# DRL.net
KiCad netlist of a schematic drawn in Altium Designer
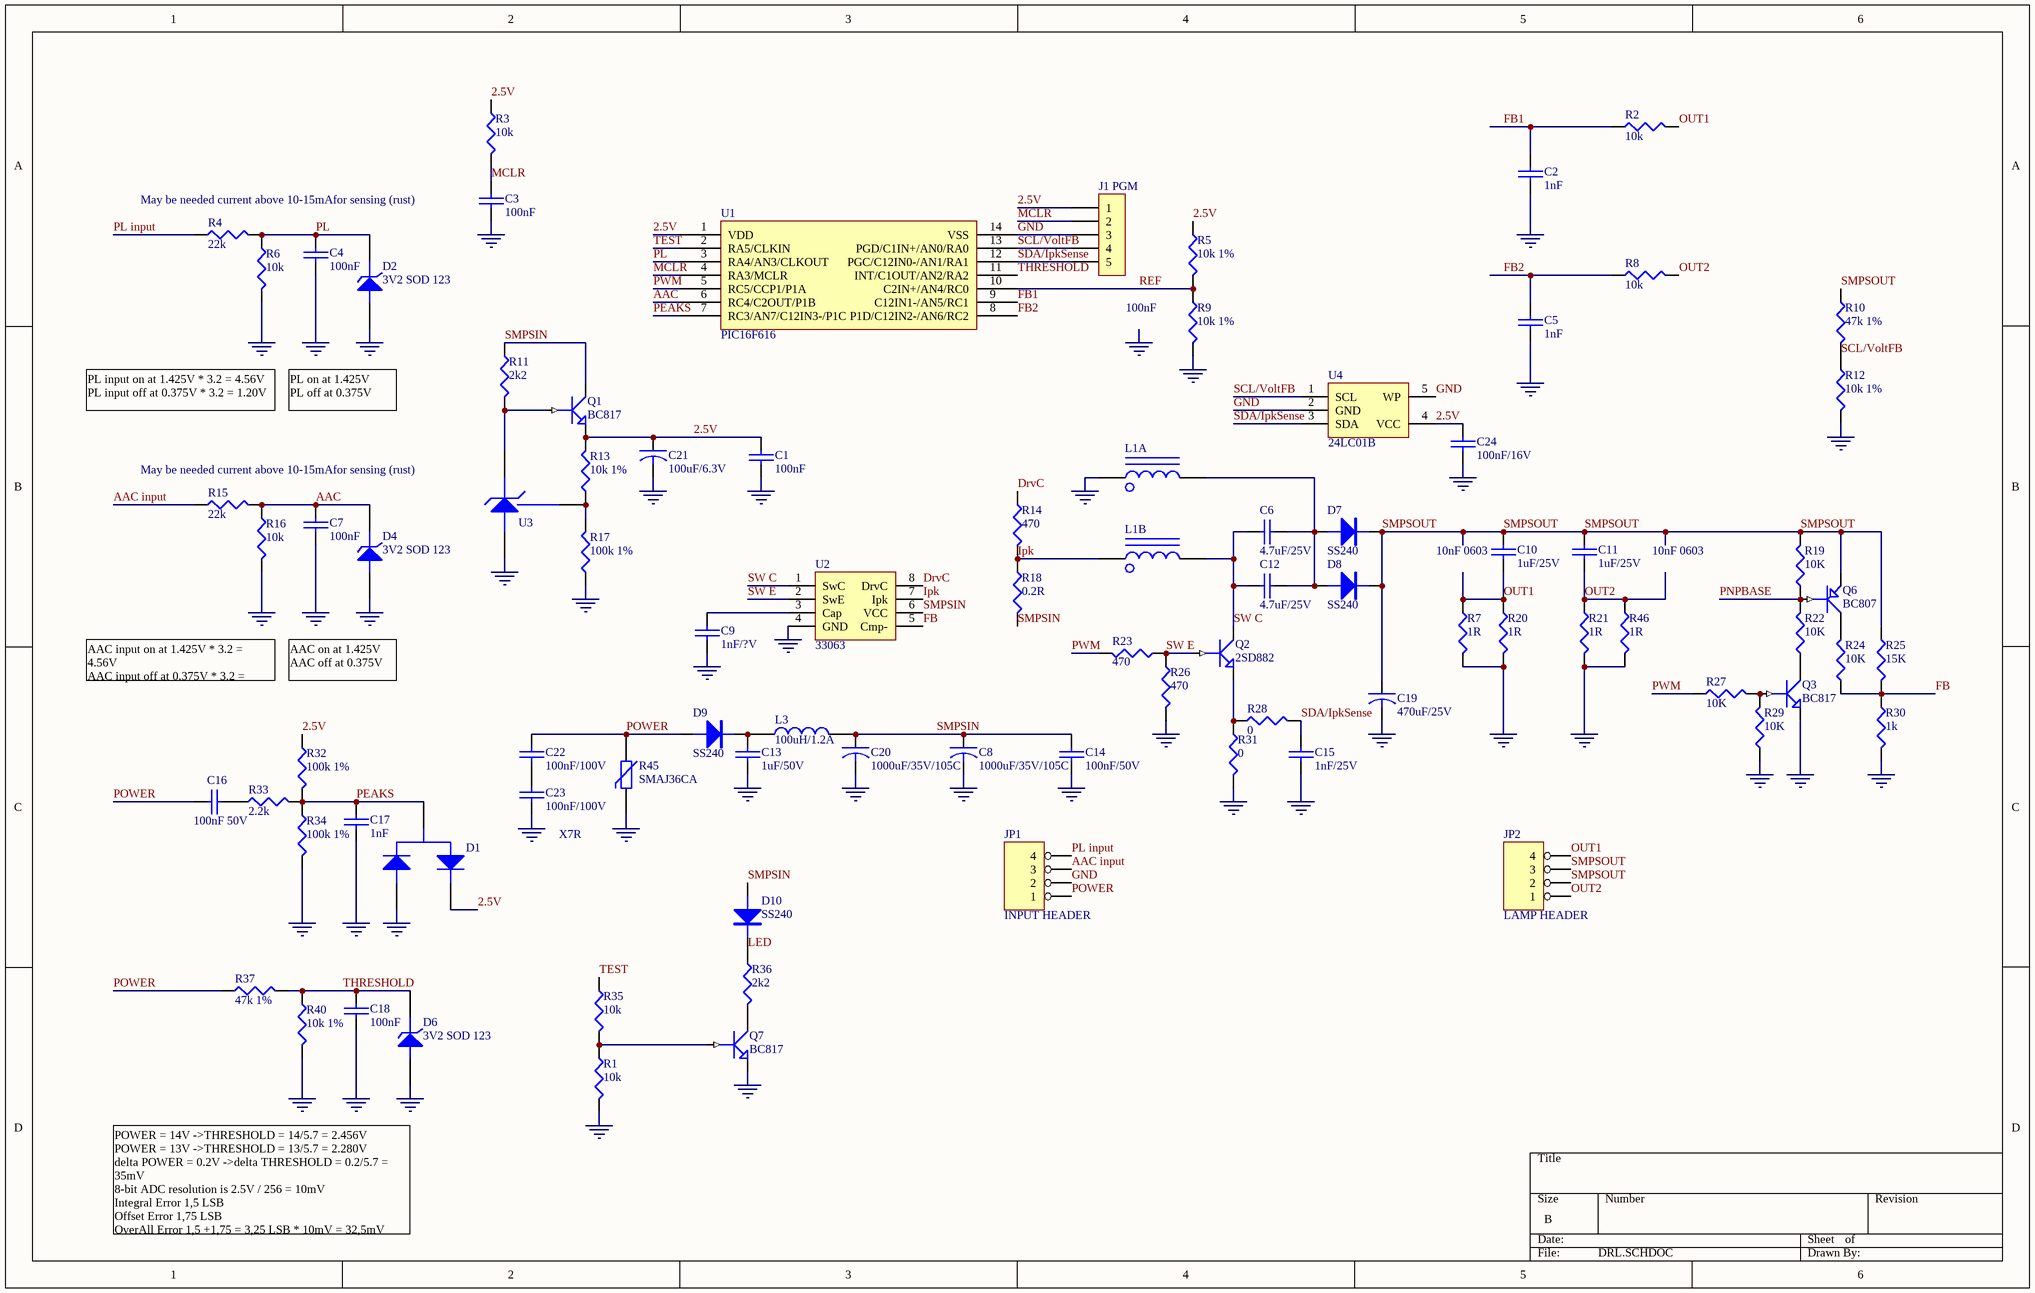
[diagram p0: DRL.SCHDOC]

(export (version "E")
  (design (tool "Eeschema 10.0.6"))
  (components
    (comp (ref "C1")
      (value "100nF")
      (footprint "0603")
      (description "Capacitor")
      (libsource (lib "Miscellaneous Devices") (part "CAP"))
    )
    (comp (ref "C2")
      (value "1nF")
      (footprint "0603")
      (description "Capacitor")
      (libsource (lib "Miscellaneous Devices") (part "CAP"))
    )
    (comp (ref "C3")
      (value "100nF")
      (footprint "0603")
      (description "Capacitor")
      (libsource (lib "Miscellaneous Devices") (part "CAP"))
    )
    (comp (ref "C4")
      (value "100nF")
      (footprint "0603")
      (description "Capacitor")
      (libsource (lib "Miscellaneous Devices") (part "CAP"))
    )
    (comp (ref "C5")
      (value "1nF")
      (footprint "0603")
      (description "Capacitor")
      (libsource (lib "Miscellaneous Devices") (part "CAP"))
    )
    (comp (ref "C6")
      (value "4.7uF/25V")
      (footprint "0805")
      (description "Capacitor")
      (libsource (lib "Miscellaneous Devices") (part "CAP"))
    )
    (comp (ref "C7")
      (value "100nF")
      (footprint "0603")
      (description "Capacitor")
      (libsource (lib "Miscellaneous Devices") (part "CAP"))
    )
    (comp (ref "C8")
      (value "1000uF/35V/105C")
      (footprint "RA 13mm")
      (description "Capacitor")
      (libsource (lib "Miscellaneous Devices") (part "CAPACITOR"))
    )
    (comp (ref "C9")
      (value "1nF/?V")
      (footprint "0603")
      (description "Capacitor")
      (libsource (lib "Miscellaneous Devices") (part "CAP"))
    )
    (comp (ref "C10")
      (value "1uF/25V")
      (footprint "0805")
      (description "Capacitor")
      (libsource (lib "Miscellaneous Devices") (part "CAP"))
    )
    (comp (ref "C11")
      (value "1uF/25V")
      (footprint "0805")
      (description "Capacitor")
      (libsource (lib "Miscellaneous Devices") (part "CAP"))
    )
    (comp (ref "C12")
      (value "4.7uF/25V")
      (footprint "0805")
      (description "Capacitor")
      (libsource (lib "Miscellaneous Devices") (part "CAP"))
    )
    (comp (ref "C13")
      (value "1uF/50V")
      (footprint "0805")
      (description "Capacitor")
      (libsource (lib "Miscellaneous Devices") (part "CAP"))
    )
    (comp (ref "C14")
      (value "100nF/50V")
      (footprint "0603")
      (description "Capacitor")
      (libsource (lib "Miscellaneous Devices") (part "CAP"))
    )
    (comp (ref "C15")
      (value "1nF/25V")
      (footprint "0603")
      (description "Capacitor")
      (libsource (lib "Miscellaneous Devices") (part "CAP"))
    )
    (comp (ref "C16")
      (value "100nF 50V")
      (footprint "0805")
      (description "Capacitor")
      (libsource (lib "Miscellaneous Devices") (part "CAP"))
    )
    (comp (ref "C17")
      (value "1nF")
      (footprint "0603")
      (description "Capacitor")
      (libsource (lib "Miscellaneous Devices") (part "CAP"))
    )
    (comp (ref "C18")
      (value "100nF")
      (footprint "0603")
      (description "Capacitor")
      (libsource (lib "Miscellaneous Devices") (part "CAP"))
    )
    (comp (ref "C19")
      (value "470uF/25V")
      (footprint "CS 10.3")
      (description "Capacitor")
      (libsource (lib "Miscellaneous Devices") (part "CAPACITOR"))
    )
    (comp (ref "C20")
      (value "1000uF/35V/105C")
      (footprint "RA 13mm")
      (description "Capacitor")
      (libsource (lib "Miscellaneous Devices") (part "CAPACITOR"))
    )
    (comp (ref "C21")
      (value "100uF/6.3V")
      (footprint "CS 6.6")
      (description "Capacitor")
      (libsource (lib "Miscellaneous Devices") (part "CAPACITOR"))
    )
    (comp (ref "C22")
      (value "100nF/100V")
      (footprint "0603")
      (description "Capacitor")
      (libsource (lib "Miscellaneous Devices") (part "CAP"))
    )
    (comp (ref "C23")
      (value "100nF/100V")
      (footprint "0603")
      (description "Capacitor")
      (libsource (lib "Miscellaneous Devices") (part "CAP"))
    )
    (comp (ref "C24")
      (value "100nF/16V")
      (footprint "0603")
      (description "Capacitor")
      (libsource (lib "Miscellaneous Devices") (part "CAP"))
    )
    (comp (ref "D1")
      (value "DUAL DIODE BAV99")
      (footprint "SOT-23")
      (libsource (lib "Devices") (part "DUAL DIODE BAV99"))
    )
    (comp (ref "D2")
      (value "3V2 SOD 123")
      (footprint "SOD 123")
      (description "Zener Diode")
      (libsource (lib "Miscellaneous Devices") (part "ZENER3"))
    )
    (comp (ref "D4")
      (value "3V2 SOD 123")
      (footprint "SOD 123")
      (description "Zener Diode")
      (libsource (lib "Miscellaneous Devices") (part "ZENER3"))
    )
    (comp (ref "D6")
      (value "3V2 SOD 123")
      (footprint "SOD 123")
      (description "Zener Diode")
      (libsource (lib "Miscellaneous Devices") (part "ZENER3"))
    )
    (comp (ref "D7")
      (value "SS240")
      (footprint "SMA")
      (description "Diode")
      (libsource (lib "") (part "DIODE_1"))
    )
    (comp (ref "D8")
      (value "SS240")
      (footprint "SMA")
      (description "Diode")
      (libsource (lib "") (part "DIODE_1"))
    )
    (comp (ref "D9")
      (value "SS240")
      (footprint "SMA")
      (description "Diode")
      (libsource (lib "") (part "DIODE_1"))
    )
    (comp (ref "D10")
      (value "SS240")
      (footprint "SIP2")
      (description "Diode")
      (libsource (lib "Miscellaneous Devices") (part "DIODE"))
    )
    (comp (ref "J1")
      (value "PGM")
      (footprint "SIP5 1.27")
      (description "Connector")
      (libsource (lib "Miscellaneous Devices") (part "CON5"))
    )
    (comp (ref "JP1")
      (value "INPUT HEADER")
      (footprint "SIP4 5.1")
      (description "4 Pin Header")
      (libsource (lib "Miscellaneous Devices") (part "4 HEADER"))
    )
    (comp (ref "JP2")
      (value "LAMP HEADER")
      (footprint "SIP4 4.0")
      (description "4 Pin Header")
      (libsource (lib "Miscellaneous Devices") (part "4 HEADER"))
    )
    (comp (ref "L1")
      (value "~")
      (footprint "DUAL IND")
      (libsource (lib "Miscellaneous Devices") (part "INDICTOR SEPIC"))
    )
    (comp (ref "L3")
      (value "100uH/1.2A")
      (footprint "IND SINGLE")
      (libsource (lib "Miscellaneous Devices") (part "INDUCTOR"))
    )
    (comp (ref "Q1")
      (value "BC817")
      (footprint "SOT-23")
      (description "NPN Transistor")
      (libsource (lib "Miscellaneous Devices") (part "NPN1"))
    )
    (comp (ref "Q2")
      (value "2SD882")
      (footprint "SOT-89")
      (description "NPN Transistor")
      (libsource (lib "Miscellaneous Devices") (part "NPN1"))
    )
    (comp (ref "Q3")
      (value "BC817")
      (footprint "SOT-23")
      (description "NPN Transistor")
      (libsource (lib "Miscellaneous Devices") (part "NPN1"))
    )
    (comp (ref "Q6")
      (value "BC807")
      (footprint "SOT-23")
      (description "PNP Transistor")
      (libsource (lib "Miscellaneous Devices") (part "PNP1"))
    )
    (comp (ref "Q7")
      (value "BC817")
      (footprint "SOT-23")
      (description "NPN Transistor")
      (libsource (lib "Miscellaneous Devices") (part "NPN1"))
    )
    (comp (ref "R1") (value "10k") (footprint "0603") (libsource (lib "Miscellaneous Devices") (part "RES1")))
    (comp (ref "R2") (value "10k") (footprint "0603") (libsource (lib "Miscellaneous Devices") (part "RES1")))
    (comp (ref "R3") (value "10k") (footprint "0603") (libsource (lib "Miscellaneous Devices") (part "RES1")))
    (comp (ref "R4") (value "22k") (footprint "0805") (libsource (lib "Miscellaneous Devices") (part "RES1")))
    (comp (ref "R5")
      (value "10k 1%")
      (footprint "0603")
      (libsource (lib "Miscellaneous Devices") (part "RES1"))
    )
    (comp (ref "R6") (value "10k") (footprint "0603") (libsource (lib "Miscellaneous Devices") (part "RES1")))
    (comp (ref "R7") (value "1R") (footprint "1206") (libsource (lib "Miscellaneous Devices") (part "RES1")))
    (comp (ref "R8") (value "10k") (footprint "0603") (libsource (lib "Miscellaneous Devices") (part "RES1")))
    (comp (ref "R9")
      (value "10k 1%")
      (footprint "0603")
      (libsource (lib "Miscellaneous Devices") (part "RES1"))
    )
    (comp (ref "R10")
      (value "47k 1%")
      (footprint "0603")
      (libsource (lib "Miscellaneous Devices") (part "RES1"))
    )
    (comp (ref "R11")
      (value "2k2")
      (footprint "0603")
      (libsource (lib "Miscellaneous Devices") (part "RES1"))
    )
    (comp (ref "R12")
      (value "10k 1%")
      (footprint "0603")
      (libsource (lib "Miscellaneous Devices") (part "RES1"))
    )
    (comp (ref "R13")
      (value "10k 1%")
      (footprint "0603")
      (libsource (lib "Miscellaneous Devices") (part "RES1"))
    )
    (comp (ref "R14")
      (value "470")
      (footprint "0603")
      (libsource (lib "Miscellaneous Devices") (part "RES1"))
    )
    (comp (ref "R15")
      (value "22k")
      (footprint "0805")
      (libsource (lib "Miscellaneous Devices") (part "RES1"))
    )
    (comp (ref "R16")
      (value "10k")
      (footprint "0603")
      (libsource (lib "Miscellaneous Devices") (part "RES1"))
    )
    (comp (ref "R17")
      (value "100k 1%")
      (footprint "0603")
      (libsource (lib "Miscellaneous Devices") (part "RES1"))
    )
    (comp (ref "R18")
      (value "0.2R")
      (footprint "1206")
      (libsource (lib "Miscellaneous Devices") (part "RES1"))
    )
    (comp (ref "R19")
      (value "10K")
      (footprint "0603")
      (libsource (lib "Miscellaneous Devices") (part "RES1"))
    )
    (comp (ref "R20") (value "1R") (footprint "1206") (libsource (lib "Miscellaneous Devices") (part "RES1")))
    (comp (ref "R21") (value "1R") (footprint "1206") (libsource (lib "Miscellaneous Devices") (part "RES1")))
    (comp (ref "R22")
      (value "10K")
      (footprint "0603")
      (libsource (lib "Miscellaneous Devices") (part "RES1"))
    )
    (comp (ref "R23")
      (value "470")
      (footprint "0603")
      (libsource (lib "Miscellaneous Devices") (part "RES1"))
    )
    (comp (ref "R24")
      (value "10K")
      (footprint "0603")
      (libsource (lib "Miscellaneous Devices") (part "RES1"))
    )
    (comp (ref "R25")
      (value "15K")
      (footprint "0603")
      (libsource (lib "Miscellaneous Devices") (part "RES1"))
    )
    (comp (ref "R26")
      (value "470")
      (footprint "0603")
      (libsource (lib "Miscellaneous Devices") (part "RES1"))
    )
    (comp (ref "R27")
      (value "10K")
      (footprint "0603")
      (libsource (lib "Miscellaneous Devices") (part "RES1"))
    )
    (comp (ref "R28") (value "0") (footprint "0603") (libsource (lib "Miscellaneous Devices") (part "RES1")))
    (comp (ref "R29")
      (value "10K")
      (footprint "0603")
      (libsource (lib "Miscellaneous Devices") (part "RES1"))
    )
    (comp (ref "R30") (value "1k") (footprint "0603") (libsource (lib "Miscellaneous Devices") (part "RES1")))
    (comp (ref "R31") (value "0") (footprint "1206") (libsource (lib "Miscellaneous Devices") (part "RES1")))
    (comp (ref "R32")
      (value "100k 1%")
      (footprint "0603")
      (libsource (lib "Miscellaneous Devices") (part "RES1"))
    )
    (comp (ref "R33")
      (value "2.2k")
      (footprint "0603")
      (libsource (lib "Miscellaneous Devices") (part "RES1"))
    )
    (comp (ref "R34")
      (value "100k 1%")
      (footprint "0603")
      (libsource (lib "Miscellaneous Devices") (part "RES1"))
    )
    (comp (ref "R35")
      (value "10k")
      (footprint "0603")
      (libsource (lib "Miscellaneous Devices") (part "RES1"))
    )
    (comp (ref "R36")
      (value "2k2")
      (footprint "0805")
      (libsource (lib "Miscellaneous Devices") (part "RES1"))
    )
    (comp (ref "R37")
      (value "47k 1%")
      (footprint "0603")
      (libsource (lib "Miscellaneous Devices") (part "RES1"))
    )
    (comp (ref "R40")
      (value "10k 1%")
      (footprint "0603")
      (libsource (lib "Miscellaneous Devices") (part "RES1"))
    )
    (comp (ref "R45")
      (value "SMAJ36CA")
      (footprint "SMA")
      (libsource (lib "Miscellaneous Devices") (part "VARISTOR"))
    )
    (comp (ref "R46") (value "1R") (footprint "1206") (libsource (lib "Miscellaneous Devices") (part "RES1")))
    (comp (ref "U1")
      (value "PIC16F616")
      (footprint "SO-14")
      (description "Microchip Microcontroller")
      (libsource (lib "MCU") (part "PIC16F616"))
    )
    (comp (ref "U2")
      (value "33063")
      (footprint "SO-8")
      (description "DC/DC converter")
      (libsource (lib "Devices") (part "34063"))
    )
    (comp (ref "U3") (value "TL431") (footprint "SOT-23") (libsource (lib "Devices") (part "TL431")))
    (comp (ref "U4")
      (value "24LC01B")
      (footprint "SOT23 - 5")
      (libsource (lib "Devices") (part "MEMORY I2C SOT23"))
    )
  )
  (nets
    (net (code "1") (name "/2.5V") (class "Default")
      (node (ref "C1") (pin "1") (pinfunction "1_1") (pintype "passive"))
      (node (ref "C21") (pin "1") (pinfunction "1_1") (pintype "passive"))
      (node (ref "C24") (pin "1") (pinfunction "1_1") (pintype "passive"))
      (node (ref "D1") (pin "3") (pinfunction "K_3") (pintype "passive"))
      (node (ref "J1") (pin "1") (pinfunction "1_1") (pintype "passive"))
      (node (ref "Q1") (pin "3") (pinfunction "E_3") (pintype "passive"))
      (node (ref "R13") (pin "2") (pinfunction "2_2") (pintype "passive"))
      (node (ref "R3") (pin "1") (pinfunction "1_1") (pintype "passive"))
      (node (ref "R32") (pin "1") (pinfunction "1_1") (pintype "passive"))
      (node (ref "R5") (pin "1") (pinfunction "1_1") (pintype "passive"))
      (node (ref "U1") (pin "1") (pinfunction "VDD_1") (pintype "passive"))
      (node (ref "U4") (pin "4") (pinfunction "VCC_4") (pintype "passive"))
    )
    (net (code "2") (name "/AAC") (class "Default")
      (node (ref "C7") (pin "1") (pinfunction "1_1") (pintype "passive"))
      (node (ref "D4") (pin "2") (pinfunction "K_2") (pintype "passive"))
      (node (ref "R15") (pin "2") (pinfunction "2_2") (pintype "passive"))
      (node (ref "R16") (pin "1") (pinfunction "1_1") (pintype "passive"))
      (node (ref "U1") (pin "6") (pinfunction "RC4/C2OUT/P1B_6") (pintype "passive"))
    )
    (net (code "3") (name "/AAC input") (class "Default")
      (node (ref "JP1") (pin "3") (pinfunction "3_3") (pintype "passive"))
      (node (ref "R15") (pin "1") (pinfunction "1_1") (pintype "passive"))
    )
    (net (code "4") (name "/DrvC") (class "Default")
      (node (ref "R14") (pin "1") (pinfunction "1_1") (pintype "passive"))
      (node (ref "U2") (pin "8") (pinfunction "DrvC_8") (pintype "passive"))
    )
    (net (code "5") (name "/FB") (class "Default")
      (node (ref "R24") (pin "1") (pinfunction "1_1") (pintype "passive"))
      (node (ref "R25") (pin "2") (pinfunction "2_2") (pintype "passive"))
      (node (ref "R30") (pin "1") (pinfunction "1_1") (pintype "passive"))
      (node (ref "U2") (pin "5") (pinfunction "Cmp-_5") (pintype "passive"))
    )
    (net (code "6") (name "/FB1") (class "Default")
      (node (ref "C2") (pin "1") (pinfunction "1_1") (pintype "passive"))
      (node (ref "R2") (pin "1") (pinfunction "1_1") (pintype "passive"))
      (node (ref "U1") (pin "9") (pinfunction "C12IN1-/AN5/RC1_9") (pintype "passive"))
    )
    (net (code "7") (name "/FB2") (class "Default")
      (node (ref "C5") (pin "1") (pinfunction "1_1") (pintype "passive"))
      (node (ref "R8") (pin "1") (pinfunction "1_1") (pintype "passive"))
      (node (ref "U1") (pin "8") (pinfunction "P1D/C12IN2-/AN6/RC2_8") (pintype "passive"))
    )
    (net (code "8") (name "/Ipk") (class "Default")
      (node (ref "L1") (pin "2") (pinfunction "2_2") (pintype "passive"))
      (node (ref "R14") (pin "2") (pinfunction "2_2") (pintype "passive"))
      (node (ref "R18") (pin "1") (pinfunction "1_1") (pintype "passive"))
      (node (ref "U2") (pin "7") (pinfunction "Ipk_7") (pintype "passive"))
    )
    (net (code "9") (name "/LED") (class "Default")
      (node (ref "D10") (pin "2") (pinfunction "K_2") (pintype "passive"))
      (node (ref "R36") (pin "1") (pinfunction "1_1") (pintype "passive"))
    )
    (net (code "10") (name "/MCLR") (class "Default")
      (node (ref "C3") (pin "1") (pinfunction "1_1") (pintype "passive"))
      (node (ref "J1") (pin "2") (pinfunction "2_2") (pintype "passive"))
      (node (ref "R3") (pin "2") (pinfunction "2_2") (pintype "passive"))
      (node (ref "U1") (pin "4") (pinfunction "RA3/MCLR_4") (pintype "passive"))
    )
    (net (code "11") (name "/OUT1") (class "Default")
      (node (ref "C10") (pin "2") (pinfunction "2_2") (pintype "passive"))
      (node (ref "JP2") (pin "4") (pinfunction "4_4") (pintype "passive"))
      (node (ref "R2") (pin "2") (pinfunction "2_2") (pintype "passive"))
      (node (ref "R20") (pin "1") (pinfunction "1_1") (pintype "passive"))
      (node (ref "R7") (pin "1") (pinfunction "1_1") (pintype "passive"))
    )
    (net (code "12") (name "/OUT2") (class "Default")
      (node (ref "C11") (pin "2") (pinfunction "2_2") (pintype "passive"))
      (node (ref "JP2") (pin "1") (pinfunction "1_1") (pintype "passive"))
      (node (ref "R21") (pin "1") (pinfunction "1_1") (pintype "passive"))
      (node (ref "R46") (pin "1") (pinfunction "1_1") (pintype "passive"))
      (node (ref "R8") (pin "2") (pinfunction "2_2") (pintype "passive"))
    )
    (net (code "13") (name "/PEAKS") (class "Default")
      (node (ref "C17") (pin "1") (pinfunction "1_1") (pintype "passive"))
      (node (ref "D1") (pin "2") (pinfunction "AK_2") (pintype "passive"))
      (node (ref "R32") (pin "2") (pinfunction "2_2") (pintype "passive"))
      (node (ref "R33") (pin "2") (pinfunction "2_2") (pintype "passive"))
      (node (ref "R34") (pin "1") (pinfunction "1_1") (pintype "passive"))
      (node (ref "U1") (pin "7") (pinfunction "RC3/AN7/C12IN3-/P1C_7") (pintype "passive"))
    )
    (net (code "14") (name "/PL") (class "Default")
      (node (ref "C4") (pin "1") (pinfunction "1_1") (pintype "passive"))
      (node (ref "D2") (pin "2") (pinfunction "K_2") (pintype "passive"))
      (node (ref "R4") (pin "2") (pinfunction "2_2") (pintype "passive"))
      (node (ref "R6") (pin "1") (pinfunction "1_1") (pintype "passive"))
      (node (ref "U1") (pin "3") (pinfunction "RA4/AN3/CLKOUT_3") (pintype "passive"))
    )
    (net (code "15") (name "/PL input") (class "Default")
      (node (ref "JP1") (pin "4") (pinfunction "4_4") (pintype "passive"))
      (node (ref "R4") (pin "1") (pinfunction "1_1") (pintype "passive"))
    )
    (net (code "16") (name "/PNPBASE") (class "Default")
      (node (ref "Q6") (pin "1") (pinfunction "B_1") (pintype "input"))
      (node (ref "R19") (pin "1") (pinfunction "1_1") (pintype "passive"))
      (node (ref "R22") (pin "2") (pinfunction "2_2") (pintype "passive"))
    )
    (net (code "17") (name "/POWER") (class "Default")
      (node (ref "C16") (pin "1") (pinfunction "1_1") (pintype "passive"))
      (node (ref "C22") (pin "1") (pinfunction "1_1") (pintype "passive"))
      (node (ref "D9") (pin "A") (pinfunction "A_A") (pintype "passive"))
      (node (ref "JP1") (pin "1") (pinfunction "1_1") (pintype "passive"))
      (node (ref "R37") (pin "1") (pinfunction "1_1") (pintype "passive"))
      (node (ref "R45") (pin "A") (pinfunction "1_A") (pintype "passive"))
    )
    (net (code "18") (name "/PWM") (class "Default")
      (node (ref "R23") (pin "2") (pinfunction "2_2") (pintype "passive"))
      (node (ref "R27") (pin "1") (pinfunction "1_1") (pintype "passive"))
      (node (ref "U1") (pin "5") (pinfunction "RC5/CCP1/P1A_5") (pintype "passive"))
    )
    (net (code "19") (name "/REF") (class "Default")
      (node (ref "R5") (pin "2") (pinfunction "2_2") (pintype "passive"))
      (node (ref "R9") (pin "1") (pinfunction "1_1") (pintype "passive"))
      (node (ref "U1") (pin "10") (pinfunction "C2IN+/AN4/RC0_10") (pintype "passive"))
    )
    (net (code "20") (name "/SCL{slash}VoltFB") (class "Default")
      (node (ref "J1") (pin "4") (pinfunction "4_4") (pintype "passive"))
      (node (ref "R10") (pin "2") (pinfunction "2_2") (pintype "passive"))
      (node (ref "R12") (pin "1") (pinfunction "1_1") (pintype "passive"))
      (node (ref "U1") (pin "13") (pinfunction "PGD/C1IN+/AN0/RA0_13") (pintype "passive"))
      (node (ref "U4") (pin "1") (pinfunction "SCL_1") (pintype "passive"))
    )
    (net (code "21") (name "/SDA{slash}IpkSense") (class "Default")
      (node (ref "C15") (pin "1") (pinfunction "1_1") (pintype "passive"))
      (node (ref "J1") (pin "5") (pinfunction "5_5") (pintype "passive"))
      (node (ref "R28") (pin "2") (pinfunction "2_2") (pintype "passive"))
      (node (ref "U1") (pin "12") (pinfunction "PGC/C12IN0-/AN1/RA1_12") (pintype "passive"))
      (node (ref "U4") (pin "3") (pinfunction "SDA_3") (pintype "passive"))
    )
    (net (code "22") (name "/SMPSIN") (class "Default")
      (node (ref "C14") (pin "1") (pinfunction "1_1") (pintype "passive"))
      (node (ref "C20") (pin "1") (pinfunction "1_1") (pintype "passive"))
      (node (ref "C8") (pin "1") (pinfunction "1_1") (pintype "passive"))
      (node (ref "D10") (pin "1") (pinfunction "A_1") (pintype "passive"))
      (node (ref "L3") (pin "2") (pinfunction "2_2") (pintype "passive"))
      (node (ref "Q1") (pin "2") (pinfunction "C_2") (pintype "passive"))
      (node (ref "R11") (pin "1") (pinfunction "1_1") (pintype "passive"))
      (node (ref "R18") (pin "2") (pinfunction "2_2") (pintype "passive"))
      (node (ref "U2") (pin "6") (pinfunction "VCC_6") (pintype "passive"))
    )
    (net (code "23") (name "/SMPSOUT") (class "Default")
      (node (ref "C10") (pin "1") (pinfunction "1_1") (pintype "passive"))
      (node (ref "C11") (pin "1") (pinfunction "1_1") (pintype "passive"))
      (node (ref "C19") (pin "1") (pinfunction "1_1") (pintype "passive"))
      (node (ref "D7") (pin "K") (pinfunction "K_K") (pintype "passive"))
      (node (ref "D8") (pin "K") (pinfunction "K_K") (pintype "passive"))
      (node (ref "JP2") (pin "2") (pinfunction "2_2") (pintype "passive"))
      (node (ref "JP2") (pin "3") (pinfunction "3_3") (pintype "passive"))
      (node (ref "Q6") (pin "3") (pinfunction "E_3") (pintype "passive"))
      (node (ref "R10") (pin "1") (pinfunction "1_1") (pintype "passive"))
      (node (ref "R19") (pin "2") (pinfunction "2_2") (pintype "passive"))
      (node (ref "R25") (pin "1") (pinfunction "1_1") (pintype "passive"))
    )
    (net (code "24") (name "/SW C") (class "Default")
      (node (ref "C12") (pin "1") (pinfunction "1_1") (pintype "passive"))
      (node (ref "C6") (pin "1") (pinfunction "1_1") (pintype "passive"))
      (node (ref "L1") (pin "4") (pinfunction "4_4") (pintype "passive"))
      (node (ref "Q2") (pin "2") (pinfunction "C_2") (pintype "passive"))
      (node (ref "U2") (pin "1") (pinfunction "SwC_1") (pintype "passive"))
    )
    (net (code "25") (name "/SW E") (class "Default")
      (node (ref "Q2") (pin "1") (pinfunction "B_1") (pintype "input"))
      (node (ref "R23") (pin "1") (pinfunction "1_1") (pintype "passive"))
      (node (ref "R26") (pin "1") (pinfunction "1_1") (pintype "passive"))
      (node (ref "U2") (pin "2") (pinfunction "SwE_2") (pintype "passive"))
    )
    (net (code "26") (name "/TEST") (class "Default")
      (node (ref "R35") (pin "1") (pinfunction "1_1") (pintype "passive"))
      (node (ref "U1") (pin "2") (pinfunction "RA5/CLKIN_2") (pintype "passive"))
    )
    (net (code "27") (name "/THRESHOLD") (class "Default")
      (node (ref "C18") (pin "1") (pinfunction "1_1") (pintype "passive"))
      (node (ref "D6") (pin "2") (pinfunction "K_2") (pintype "passive"))
      (node (ref "R37") (pin "2") (pinfunction "2_2") (pintype "passive"))
      (node (ref "R40") (pin "1") (pinfunction "1_1") (pintype "passive"))
      (node (ref "U1") (pin "11") (pinfunction "INT/C1OUT/AN2/RA2_11") (pintype "passive"))
    )
    (net (code "28") (name "GND") (class "Default")
      (node (ref "C1") (pin "2") (pinfunction "2_2") (pintype "passive"))
      (node (ref "C13") (pin "2") (pinfunction "2_2") (pintype "passive"))
      (node (ref "C14") (pin "2") (pinfunction "2_2") (pintype "passive"))
      (node (ref "C15") (pin "2") (pinfunction "2_2") (pintype "passive"))
      (node (ref "C17") (pin "2") (pinfunction "2_2") (pintype "passive"))
      (node (ref "C18") (pin "2") (pinfunction "2_2") (pintype "passive"))
      (node (ref "C19") (pin "2") (pinfunction "2_2") (pintype "passive"))
      (node (ref "C2") (pin "2") (pinfunction "2_2") (pintype "passive"))
      (node (ref "C20") (pin "2") (pinfunction "2_2") (pintype "passive"))
      (node (ref "C21") (pin "2") (pinfunction "2_2") (pintype "passive"))
      (node (ref "C23") (pin "2") (pinfunction "2_2") (pintype "passive"))
      (node (ref "C24") (pin "2") (pinfunction "2_2") (pintype "passive"))
      (node (ref "C3") (pin "2") (pinfunction "2_2") (pintype "passive"))
      (node (ref "C4") (pin "2") (pinfunction "2_2") (pintype "passive"))
      (node (ref "C5") (pin "2") (pinfunction "2_2") (pintype "passive"))
      (node (ref "C7") (pin "2") (pinfunction "2_2") (pintype "passive"))
      (node (ref "C8") (pin "2") (pinfunction "2_2") (pintype "passive"))
      (node (ref "C9") (pin "2") (pinfunction "2_2") (pintype "passive"))
      (node (ref "D1") (pin "1") (pinfunction "A_1") (pintype "passive"))
      (node (ref "D2") (pin "1") (pinfunction "A_1") (pintype "passive"))
      (node (ref "D4") (pin "1") (pinfunction "A_1") (pintype "passive"))
      (node (ref "D6") (pin "1") (pinfunction "A_1") (pintype "passive"))
      (node (ref "J1") (pin "3") (pinfunction "3_3") (pintype "passive"))
      (node (ref "JP1") (pin "2") (pinfunction "2_2") (pintype "passive"))
      (node (ref "L1") (pin "1") (pinfunction "1_1") (pintype "passive"))
      (node (ref "Q3") (pin "3") (pinfunction "E_3") (pintype "passive"))
      (node (ref "Q7") (pin "3") (pinfunction "E_3") (pintype "passive"))
      (node (ref "R1") (pin "2") (pinfunction "2_2") (pintype "passive"))
      (node (ref "R12") (pin "2") (pinfunction "2_2") (pintype "passive"))
      (node (ref "R16") (pin "2") (pinfunction "2_2") (pintype "passive"))
      (node (ref "R17") (pin "1") (pinfunction "1_1") (pintype "passive"))
      (node (ref "R20") (pin "2") (pinfunction "2_2") (pintype "passive"))
      (node (ref "R21") (pin "2") (pinfunction "2_2") (pintype "passive"))
      (node (ref "R26") (pin "2") (pinfunction "2_2") (pintype "passive"))
      (node (ref "R29") (pin "1") (pinfunction "1_1") (pintype "passive"))
      (node (ref "R30") (pin "2") (pinfunction "2_2") (pintype "passive"))
      (node (ref "R31") (pin "2") (pinfunction "2_2") (pintype "passive"))
      (node (ref "R34") (pin "2") (pinfunction "2_2") (pintype "passive"))
      (node (ref "R40") (pin "2") (pinfunction "2_2") (pintype "passive"))
      (node (ref "R45") (pin "K") (pinfunction "2_K") (pintype "passive"))
      (node (ref "R46") (pin "2") (pinfunction "2_2") (pintype "passive"))
      (node (ref "R6") (pin "2") (pinfunction "2_2") (pintype "passive"))
      (node (ref "R7") (pin "2") (pinfunction "2_2") (pintype "passive"))
      (node (ref "R9") (pin "2") (pinfunction "2_2") (pintype "passive"))
      (node (ref "U1") (pin "14") (pinfunction "VSS_14") (pintype "passive"))
      (node (ref "U2") (pin "4") (pinfunction "GND_4") (pintype "passive"))
      (node (ref "U3") (pin "2") (pinfunction "A_2") (pintype "passive"))
      (node (ref "U4") (pin "2") (pinfunction "GND_2") (pintype "passive"))
      (node (ref "U4") (pin "5") (pinfunction "WP_5") (pintype "passive"))
    )
    (net (code "29") (name "Net-(C12-Pad2)") (class "Default")
      (node (ref "C12") (pin "2") (pinfunction "2_2") (pintype "passive"))
      (node (ref "C6") (pin "2") (pinfunction "2_2") (pintype "passive"))
      (node (ref "D7") (pin "A") (pinfunction "A_A") (pintype "passive"))
      (node (ref "D8") (pin "A") (pinfunction "A_A") (pintype "passive"))
      (node (ref "L1") (pin "3") (pinfunction "3_3") (pintype "passive"))
    )
    (net (code "30") (name "Net-(C13-Pad1)") (class "Default")
      (node (ref "C13") (pin "1") (pinfunction "1_1") (pintype "passive"))
      (node (ref "D9") (pin "K") (pinfunction "K_K") (pintype "passive"))
      (node (ref "L3") (pin "1") (pinfunction "1_1") (pintype "passive"))
    )
    (net (code "31") (name "Net-(C16-Pad2)") (class "Default")
      (node (ref "C16") (pin "2") (pinfunction "2_2") (pintype "passive"))
      (node (ref "R33") (pin "1") (pinfunction "1_1") (pintype "passive"))
    )
    (net (code "32") (name "Net-(C22-Pad2)") (class "Default")
      (node (ref "C22") (pin "2") (pinfunction "2_2") (pintype "passive"))
      (node (ref "C23") (pin "1") (pinfunction "1_1") (pintype "passive"))
    )
    (net (code "33") (name "Net-(Q1-B)") (class "Default")
      (node (ref "Q1") (pin "1") (pinfunction "B_1") (pintype "input"))
      (node (ref "R11") (pin "2") (pinfunction "2_2") (pintype "passive"))
      (node (ref "U3") (pin "3") (pinfunction "K_3") (pintype "passive"))
    )
    (net (code "34") (name "Net-(Q2-E)") (class "Default")
      (node (ref "Q2") (pin "3") (pinfunction "E_3") (pintype "passive"))
      (node (ref "R28") (pin "1") (pinfunction "1_1") (pintype "passive"))
      (node (ref "R31") (pin "1") (pinfunction "1_1") (pintype "passive"))
    )
    (net (code "35") (name "Net-(Q3-B)") (class "Default")
      (node (ref "Q3") (pin "1") (pinfunction "B_1") (pintype "input"))
      (node (ref "R27") (pin "2") (pinfunction "2_2") (pintype "passive"))
      (node (ref "R29") (pin "2") (pinfunction "2_2") (pintype "passive"))
    )
    (net (code "36") (name "Net-(Q3-C)") (class "Default")
      (node (ref "Q3") (pin "2") (pinfunction "C_2") (pintype "passive"))
      (node (ref "R22") (pin "1") (pinfunction "1_1") (pintype "passive"))
    )
    (net (code "37") (name "Net-(Q6-C)") (class "Default")
      (node (ref "Q6") (pin "2") (pinfunction "C_2") (pintype "passive"))
      (node (ref "R24") (pin "2") (pinfunction "2_2") (pintype "passive"))
    )
    (net (code "38") (name "Net-(Q7-B)") (class "Default")
      (node (ref "Q7") (pin "1") (pinfunction "B_1") (pintype "input"))
      (node (ref "R1") (pin "1") (pinfunction "1_1") (pintype "passive"))
      (node (ref "R35") (pin "2") (pinfunction "2_2") (pintype "passive"))
    )
    (net (code "39") (name "Net-(Q7-C)") (class "Default")
      (node (ref "Q7") (pin "2") (pinfunction "C_2") (pintype "passive"))
      (node (ref "R36") (pin "2") (pinfunction "2_2") (pintype "passive"))
    )
    (net (code "40") (name "Net-(U2-Cap)") (class "Default")
      (node (ref "C9") (pin "1") (pinfunction "1_1") (pintype "passive"))
      (node (ref "U2") (pin "3") (pinfunction "Cap_3") (pintype "passive"))
    )
    (net (code "41") (name "Net-(U3-REF)") (class "Default")
      (node (ref "R13") (pin "1") (pinfunction "1_1") (pintype "passive"))
      (node (ref "R17") (pin "2") (pinfunction "2_2") (pintype "passive"))
      (node (ref "U3") (pin "1") (pinfunction "REF_1") (pintype "passive"))
    )
  )
)
